# 200_CDH_USB_2_Hub.net
KiCad netlist of a schematic drawn in Altium Designer
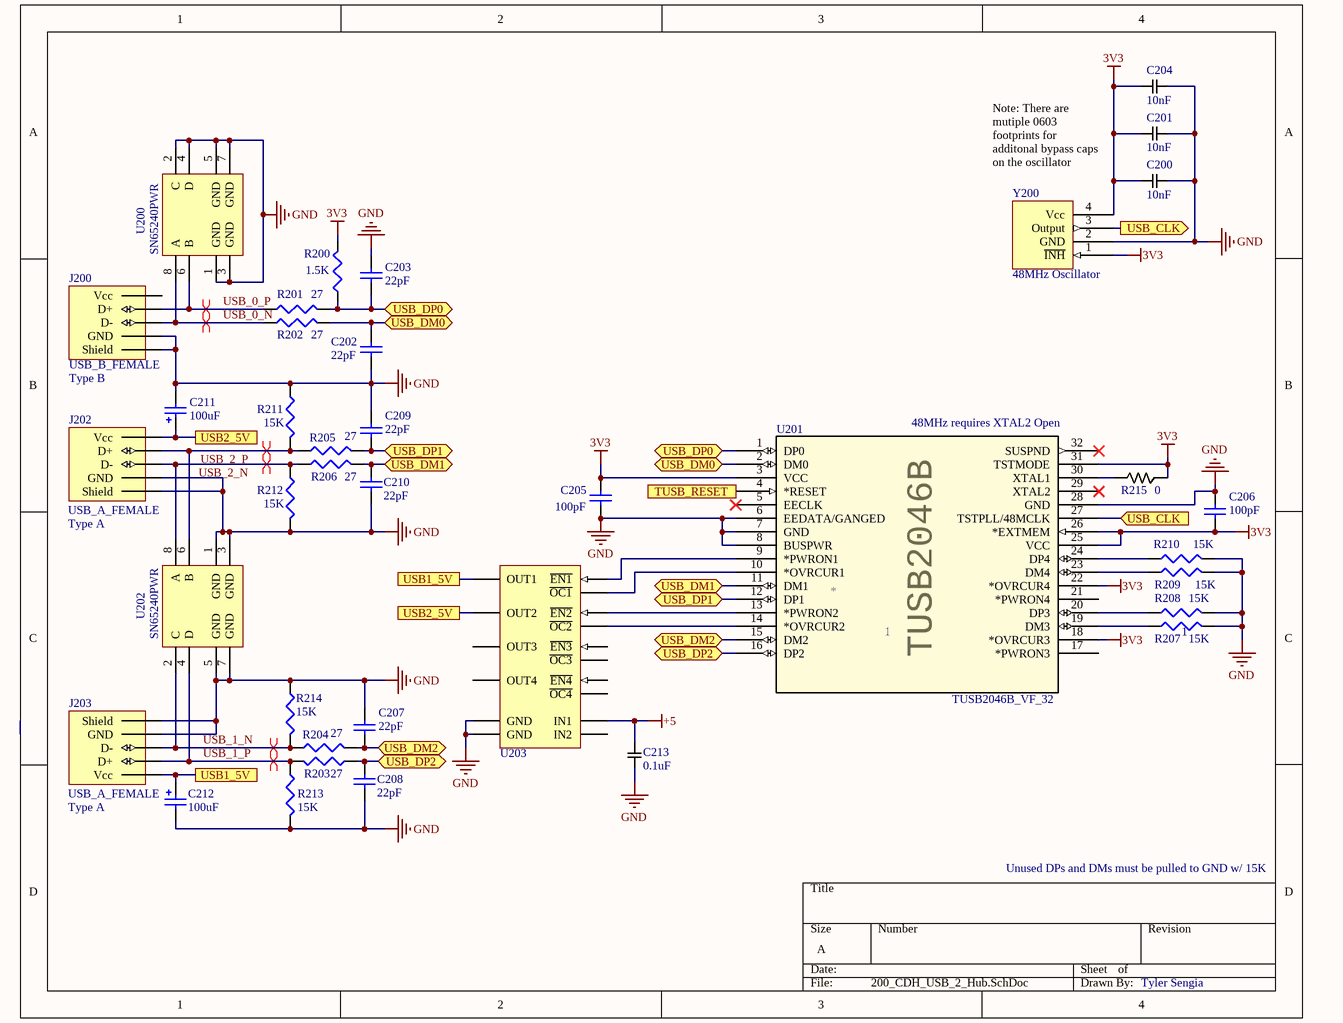
[diagram p0: 200_CDH_USB_2_Hub.SchDoc]

(export (version "E")
  (design (tool "Eeschema 10.0.6"))
  (components
    (comp (ref "C200")
      (value "10nF")
      (footprint "IMPERIAL0603_Capacitor")
      (description "10nF Capacitor for crystal oscillator")
      (fields (field (name "MANUFACTURER") "AVX") (field (name "MANUFACTURER PART NUMBER") "06033C103J4Z2A"))
      (libsource (lib "OASIS_COMPONENTS_SYMBOLS") (part "06033C103J4Z2A"))
    )
    (comp (ref "C201")
      (value "10nF")
      (footprint "IMPERIAL0603_Capacitor")
      (description "10nF Capacitor for crystal oscillator")
      (fields (field (name "MANUFACTURER") "AVX") (field (name "MANUFACTURER PART NUMBER") "06033C103J4Z2A"))
      (libsource (lib "OASIS_COMPONENTS_SYMBOLS") (part "06033C103J4Z2A"))
    )
    (comp (ref "C202")
      (value "22pF")
      (footprint "IMPERIAL0805_CAPACITOR")
      (description "22pF USB Filter Capacitor")
      (fields (field (name "Comment") "22pF capacitor") (field (name "PUBLISHER") "Altium Limited"))
      (libsource (lib "TUSB_SYMBOLS") (part "C0805X220K3GACAUTO"))
    )
    (comp (ref "C203")
      (value "22pF")
      (footprint "IMPERIAL0805_CAPACITOR")
      (description "22pF USB Filter Capacitor")
      (fields (field (name "Comment") "22pF capacitor") (field (name "PUBLISHER") "Altium Limited"))
      (libsource (lib "TUSB_SYMBOLS") (part "C0805X220K3GACAUTO"))
    )
    (comp (ref "C204")
      (value "10nF")
      (footprint "IMPERIAL0603_Capacitor")
      (description "10nF Capacitor for crystal oscillator")
      (fields (field (name "MANUFACTURER") "AVX") (field (name "MANUFACTURER PART NUMBER") "06033C103J4Z2A"))
      (libsource (lib "OASIS_COMPONENTS_SYMBOLS") (part "06033C103J4Z2A"))
    )
    (comp (ref "C205")
      (value "100pF")
      (footprint "IMPERIAL0603_Capacitor")
      (description "100pF Cap for IC Vcc Smoothing")
      (fields (field (name "Comment") "100pF Capacitor") (field (name "PUBLISHER") "Altium Limited"))
      (libsource (lib "TUSB_SYMBOLS") (part "C0603C101K8HAUTO"))
    )
    (comp (ref "C206")
      (value "100pF")
      (footprint "IMPERIAL0603_Capacitor")
      (description "100pF Cap for IC Vcc Smoothing")
      (fields (field (name "Comment") "100pF Capacitor") (field (name "PUBLISHER") "Altium Limited"))
      (libsource (lib "TUSB_SYMBOLS") (part "C0603C101K8HAUTO"))
    )
    (comp (ref "C207")
      (value "22pF")
      (footprint "IMPERIAL0805_CAPACITOR")
      (description "22pF USB Filter Capacitor")
      (fields (field (name "Comment") "22pF capacitor") (field (name "PUBLISHER") "Altium Limited"))
      (libsource (lib "TUSB_SYMBOLS") (part "C0805X220K3GACAUTO"))
    )
    (comp (ref "C208")
      (value "22pF")
      (footprint "IMPERIAL0805_CAPACITOR")
      (description "22pF USB Filter Capacitor")
      (fields (field (name "Comment") "22pF capacitor") (field (name "PUBLISHER") "Altium Limited"))
      (libsource (lib "TUSB_SYMBOLS") (part "C0805X220K3GACAUTO"))
    )
    (comp (ref "C209")
      (value "22pF")
      (footprint "IMPERIAL0805_CAPACITOR")
      (description "22pF USB Filter Capacitor")
      (fields (field (name "Comment") "22pF capacitor") (field (name "PUBLISHER") "Altium Limited"))
      (libsource (lib "TUSB_SYMBOLS") (part "C0805X220K3GACAUTO"))
    )
    (comp (ref "C210")
      (value "22pF")
      (footprint "IMPERIAL0805_CAPACITOR")
      (description "22pF USB Filter Capacitor")
      (fields (field (name "Comment") "22pF capacitor") (field (name "PUBLISHER") "Altium Limited"))
      (libsource (lib "TUSB_SYMBOLS") (part "C0805X220K3GACAUTO"))
    )
    (comp (ref "C211")
      (value "100uF")
      (footprint "POLAR_CAP_SMD_EIA2010")
      (description "100uF, USB Power smoothing capacitor, tantalium, low ESR")
      (fields (field (name "Comment") "F910J107MBAAJ6") (field (name "PUBLISHER") "Altium Limited"))
      (libsource (lib "TUSB_SYMBOLS") (part "F910J107MBAAJ6"))
    )
    (comp (ref "C212")
      (value "100uF")
      (footprint "POLAR_CAP_SMD_EIA2010")
      (description "100uF, USB Power smoothing capacitor, tantalium, low ESR")
      (fields (field (name "Comment") "F910J107MBAAJ6") (field (name "PUBLISHER") "Altium Limited"))
      (libsource (lib "TUSB_SYMBOLS") (part "F910J107MBAAJ6"))
    )
    (comp (ref "C213")
      (value "0.1uF")
      (footprint "IMPERIAL0603_Capacitor")
      (description "0.1uF Capacitor, Non Polarized Chip Cap")
      (fields (field (name "Comment") "0.1uF Capacitor"))
      (libsource (lib "OASIS_COMPONENTS_SYMBOLS") (part "VJ0603Y104MXQPW1BC"))
    )
    (comp (ref "J200")
      (value "USB_B_FEMALE")
      (footprint "USB_B_FEMALE_RT")
      (description "USB Type B female connector.")
      (fields (field (name "USB TYPE") "Type B"))
      (libsource (lib "OASIS_COMPONENTS_SYMBOLS") (part "USB_B_FEMALE"))
    )
    (comp (ref "J202")
      (value "USB_A_FEMALE")
      (footprint "USB_A_FEMALE_SINGLE")
      (description "USB Type A female connector.")
      (fields (field (name "USB TYPE") "Type A"))
      (libsource (lib "TUSB_SYMBOLS") (part "USB_A_FEMALE"))
    )
    (comp (ref "J203")
      (value "USB_A_FEMALE")
      (footprint "USB_A_FEMALE_SINGLE")
      (description "USB Type A female connector.")
      (fields (field (name "USB TYPE") "Type A"))
      (libsource (lib "") (part "USB_A_FEMALE_1"))
    )
    (comp (ref "R200")
      (value "1.5K")
      (footprint "Imperial0603_RES")
      (description "1.5KOhm Resistor, for USB pull up")
      (fields (field (name "Comment") "1.5KOhm Resistor") (field (name "PUBLISHER") "Altium Limited"))
      (libsource (lib "OASIS_COMPONENTS_SYMBOLS") (part "ERJ-S03D1501V"))
    )
    (comp (ref "R201")
      (value "27")
      (footprint "Imperial0805_RES")
      (description "27Ohm Resitor, USB Terminating Resistor")
      (fields (field (name "Comment") "27 Ohm Resistor") (field (name "PUBLISHER") "Altium Limited"))
      (libsource (lib "TUSB_SYMBOLS") (part "CR0805-FX-27R0ELF"))
    )
    (comp (ref "R202")
      (value "27")
      (footprint "Imperial0805_RES")
      (description "27Ohm Resitor, USB Terminating Resistor")
      (fields (field (name "Comment") "27 Ohm Resistor") (field (name "PUBLISHER") "Altium Limited"))
      (libsource (lib "TUSB_SYMBOLS") (part "CR0805-FX-27R0ELF"))
    )
    (comp (ref "R203")
      (value "27")
      (footprint "Imperial0805_RES")
      (description "27Ohm Resitor, USB Terminating Resistor")
      (fields (field (name "Comment") "27 Ohm Resistor") (field (name "PUBLISHER") "Altium Limited"))
      (libsource (lib "TUSB_SYMBOLS") (part "CR0805-FX-27R0ELF"))
    )
    (comp (ref "R204")
      (value "27")
      (footprint "Imperial0805_RES")
      (description "27Ohm Resitor, USB Terminating Resistor")
      (fields (field (name "Comment") "27 Ohm Resistor") (field (name "PUBLISHER") "Altium Limited"))
      (libsource (lib "TUSB_SYMBOLS") (part "CR0805-FX-27R0ELF"))
    )
    (comp (ref "R205")
      (value "27")
      (footprint "Imperial0805_RES")
      (description "27Ohm Resitor, USB Terminating Resistor")
      (fields (field (name "Comment") "27 Ohm Resistor") (field (name "PUBLISHER") "Altium Limited"))
      (libsource (lib "TUSB_SYMBOLS") (part "CR0805-FX-27R0ELF"))
    )
    (comp (ref "R206")
      (value "27")
      (footprint "Imperial0805_RES")
      (description "27Ohm Resitor, USB Terminating Resistor")
      (fields (field (name "Comment") "27 Ohm Resistor") (field (name "PUBLISHER") "Altium Limited"))
      (libsource (lib "TUSB_SYMBOLS") (part "CR0805-FX-27R0ELF"))
    )
    (comp (ref "R207")
      (value "15K")
      (footprint "Imperial0603_RES")
      (description "15KOhm Resistor, for USB pull down")
      (fields (field (name "Comment") "15KOhm Resistor") (field (name "PUBLISHER") "Altium Limited"))
      (libsource (lib "TUSB_SYMBOLS") (part "CRCW060315K0JNEAC"))
    )
    (comp (ref "R208")
      (value "15K")
      (footprint "Imperial0603_RES")
      (description "15KOhm Resistor, for USB pull down")
      (fields (field (name "Comment") "15KOhm Resistor") (field (name "PUBLISHER") "Altium Limited"))
      (libsource (lib "TUSB_SYMBOLS") (part "CRCW060315K0JNEAC"))
    )
    (comp (ref "R209")
      (value "15K")
      (footprint "Imperial0603_RES")
      (description "15KOhm Resistor, for USB pull down")
      (fields (field (name "Comment") "15KOhm Resistor") (field (name "PUBLISHER") "Altium Limited"))
      (libsource (lib "TUSB_SYMBOLS") (part "CRCW060315K0JNEAC"))
    )
    (comp (ref "R210")
      (value "15K")
      (footprint "Imperial0603_RES")
      (description "15KOhm Resistor, for USB pull down")
      (fields (field (name "Comment") "15KOhm Resistor") (field (name "PUBLISHER") "Altium Limited"))
      (libsource (lib "TUSB_SYMBOLS") (part "CRCW060315K0JNEAC"))
    )
    (comp (ref "R211")
      (value "15K")
      (footprint "Imperial0603_RES")
      (description "15KOhm Resistor, for USB pull down")
      (fields (field (name "Comment") "15KOhm Resistor") (field (name "PUBLISHER") "Altium Limited"))
      (libsource (lib "TUSB_SYMBOLS") (part "CRCW060315K0JNEAC"))
    )
    (comp (ref "R212")
      (value "15K")
      (footprint "Imperial0603_RES")
      (description "15KOhm Resistor, for USB pull down")
      (fields (field (name "Comment") "15KOhm Resistor") (field (name "PUBLISHER") "Altium Limited"))
      (libsource (lib "TUSB_SYMBOLS") (part "CRCW060315K0JNEAC"))
    )
    (comp (ref "R213")
      (value "15K")
      (footprint "Imperial0603_RES")
      (description "15KOhm Resistor, for USB pull down")
      (fields (field (name "Comment") "15KOhm Resistor") (field (name "PUBLISHER") "Altium Limited"))
      (libsource (lib "TUSB_SYMBOLS") (part "CRCW060315K0JNEAC"))
    )
    (comp (ref "R214")
      (value "15K")
      (footprint "Imperial0603_RES")
      (description "15KOhm Resistor, for USB pull down")
      (fields (field (name "Comment") "15KOhm Resistor") (field (name "PUBLISHER") "Altium Limited"))
      (libsource (lib "TUSB_SYMBOLS") (part "CRCW060315K0JNEAC"))
    )
    (comp (ref "R215")
      (value "0")
      (footprint "Imperial0603_RES")
      (description "Placeholder 0 Ohm Link.")
      (fields (field (name "Comment") "0 Ohm Link"))
      (libsource (lib "OASIS_COMPONENTS_SYMBOLS") (part "0_Ohm_Link"))
    )
    (comp (ref "U200")
      (value "SN65240PWR")
      (footprint "PW0008A_M")
      (fields (field (name "MANUFACTURER") "Texas Instruments"))
      (libsource (lib "OASIS_COMPONENTS_SYMBOLS") (part "CMP-0326-00072-3"))
    )
    (comp (ref "U201")
      (value "TUSB2046B_VF_32")
      (footprint "TQFP80P900X900X160-32N")
      (description "USB 2.0 Hub IC")
      (fields
        (field (name "MANUFACTURER_PART_NUMBER") "tusb2046b_vf_32")
        (field (name "MANUFACTURER") "Texas Instruments")
        (field (name "GENERIC_PART_NUMBER") "TUSB2046B")
      )
      (libsource (lib "OASIS_COMPONENTS_SYMBOLS") (part "TUSB2046B_VF_32"))
    )
    (comp (ref "U202")
      (value "SN65240PWR")
      (footprint "PW0008A_M")
      (fields (field (name "MANUFACTURER") "Texas Instruments"))
      (libsource (lib "") (part "CMP-0326-00072-3_1"))
    )
    (comp (ref "U203")
      (value "TPS2044BDR")
      (footprint "D0016A_M_Local")
      (fields (field (name "MANUFACTURER") "Texas Instruments"))
      (libsource (lib "OASIS_COMPONENTS_SYMBOLS") (part "TITPS10244BD1"))
    )
    (comp (ref "Y200")
      (value "48MHz Oscillator")
      (footprint "KC3225-C3")
      (description "48MHz crystal oscillator")
      (libsource (lib "OASIS_COMPONENTS_SYMBOLS") (part "KC3225A-C3"))
    )
  )
  (nets
    (net (code "1") (name "+5") (class "Default")
      (node (ref "C213") (pin "2") (pinfunction "2_2") (pintype "passive"))
      (node (ref "U203") (pin "2") (pinfunction "IN1_2") (pintype "power_in"))
    )
    (net (code "2") (name "/TUSB_RESET") (class "Default")
      (node (ref "U201") (pin "4") (pinfunction "*RESET_4") (pintype "input"))
    )
    (net (code "3") (name "/USB1_5V") (class "Default")
      (node (ref "C212") (pin "1") (pinfunction "1_1") (pintype "passive"))
      (node (ref "J203") (pin "Vcc") (pinfunction "Vcc_Vcc") (pintype "power_in"))
      (node (ref "U203") (pin "15") (pinfunction "OUT1_15") (pintype "power_in"))
    )
    (net (code "4") (name "/USB2_5V") (class "Default")
      (node (ref "C211") (pin "1") (pinfunction "1_1") (pintype "passive"))
      (node (ref "J202") (pin "Vcc") (pinfunction "Vcc_Vcc") (pintype "power_in"))
      (node (ref "U203") (pin "14") (pinfunction "OUT2_14") (pintype "power_in"))
    )
    (net (code "5") (name "/USB_0_N") (class "Default")
      (node (ref "J200") (pin "D-") (pinfunction "D-_D-") (pintype "bidirectional"))
      (node (ref "R202") (pin "1") (pinfunction "1_1") (pintype "passive"))
      (node (ref "U200") (pin "8") (pinfunction "A_8") (pintype "passive"))
    )
    (net (code "6") (name "/USB_0_P") (class "Default")
      (node (ref "J200") (pin "D+") (pinfunction "D+_D+") (pintype "bidirectional"))
      (node (ref "R201") (pin "1") (pinfunction "1_1") (pintype "passive"))
      (node (ref "U200") (pin "6") (pinfunction "B_6") (pintype "passive"))
    )
    (net (code "7") (name "/USB_1_N") (class "Default")
      (node (ref "J203") (pin "D-") (pinfunction "D-_D-") (pintype "bidirectional"))
      (node (ref "R204") (pin "2") (pinfunction "2_2") (pintype "passive"))
      (node (ref "R214") (pin "1") (pinfunction "1_1") (pintype "passive"))
      (node (ref "U202") (pin "2") (pinfunction "C_2") (pintype "passive"))
    )
    (net (code "8") (name "/USB_1_P") (class "Default")
      (node (ref "J203") (pin "D+") (pinfunction "D+_D+") (pintype "bidirectional"))
      (node (ref "R203") (pin "1") (pinfunction "1_1") (pintype "passive"))
      (node (ref "R213") (pin "2") (pinfunction "2_2") (pintype "passive"))
      (node (ref "U202") (pin "4") (pinfunction "D_4") (pintype "passive"))
    )
    (net (code "9") (name "/USB_2_N") (class "Default")
      (node (ref "J202") (pin "D-") (pinfunction "D-_D-") (pintype "bidirectional"))
      (node (ref "R206") (pin "1") (pinfunction "1_1") (pintype "passive"))
      (node (ref "R212") (pin "1") (pinfunction "1_1") (pintype "passive"))
      (node (ref "U202") (pin "8") (pinfunction "A_8") (pintype "passive"))
    )
    (net (code "10") (name "/USB_2_P") (class "Default")
      (node (ref "J202") (pin "D+") (pinfunction "D+_D+") (pintype "bidirectional"))
      (node (ref "R205") (pin "1") (pinfunction "1_1") (pintype "passive"))
      (node (ref "R211") (pin "2") (pinfunction "2_2") (pintype "passive"))
      (node (ref "U202") (pin "6") (pinfunction "B_6") (pintype "passive"))
    )
    (net (code "11") (name "/USB_CLK") (class "Default")
      (node (ref "U201") (pin "27") (pinfunction "TSTPLL/48MCLK_27") (pintype "passive"))
      (node (ref "Y200") (pin "3") (pinfunction "Output_3") (pintype "output"))
    )
    (net (code "12") (name "/USB_DM0") (class "Default")
      (node (ref "C202") (pin "2") (pinfunction "2_2") (pintype "passive"))
      (node (ref "R202") (pin "2") (pinfunction "2_2") (pintype "passive"))
      (node (ref "U201") (pin "2") (pinfunction "DM0_2") (pintype "bidirectional"))
    )
    (net (code "13") (name "/USB_DM1") (class "Default")
      (node (ref "C210") (pin "1") (pinfunction "1_1") (pintype "passive"))
      (node (ref "R206") (pin "2") (pinfunction "2_2") (pintype "passive"))
      (node (ref "U201") (pin "11") (pinfunction "DM1_11") (pintype "bidirectional"))
    )
    (net (code "14") (name "/USB_DM2") (class "Default")
      (node (ref "C207") (pin "2") (pinfunction "2_2") (pintype "passive"))
      (node (ref "R204") (pin "1") (pinfunction "1_1") (pintype "passive"))
      (node (ref "U201") (pin "15") (pinfunction "DM2_15") (pintype "bidirectional"))
    )
    (net (code "15") (name "/USB_DP0") (class "Default")
      (node (ref "C203") (pin "1") (pinfunction "1_1") (pintype "passive"))
      (node (ref "R200") (pin "1") (pinfunction "1_1") (pintype "passive"))
      (node (ref "R201") (pin "2") (pinfunction "2_2") (pintype "passive"))
      (node (ref "U201") (pin "1") (pinfunction "DP0_1") (pintype "bidirectional"))
    )
    (net (code "16") (name "/USB_DP1") (class "Default")
      (node (ref "C209") (pin "2") (pinfunction "2_2") (pintype "passive"))
      (node (ref "R205") (pin "2") (pinfunction "2_2") (pintype "passive"))
      (node (ref "U201") (pin "12") (pinfunction "DP1_12") (pintype "bidirectional"))
    )
    (net (code "17") (name "/USB_DP2") (class "Default")
      (node (ref "C208") (pin "1") (pinfunction "1_1") (pintype "passive"))
      (node (ref "R203") (pin "2") (pinfunction "2_2") (pintype "passive"))
      (node (ref "U201") (pin "16") (pinfunction "DP2_16") (pintype "bidirectional"))
    )
    (net (code "18") (name "3V3") (class "Default")
      (node (ref "C200") (pin "2") (pinfunction "2_2") (pintype "passive"))
      (node (ref "C201") (pin "2") (pinfunction "2_2") (pintype "passive"))
      (node (ref "C204") (pin "2") (pinfunction "2_2") (pintype "passive"))
      (node (ref "C205") (pin "2") (pinfunction "2_2") (pintype "passive"))
      (node (ref "C206") (pin "1") (pinfunction "1_1") (pintype "passive"))
      (node (ref "R200") (pin "2") (pinfunction "2_2") (pintype "passive"))
      (node (ref "R215") (pin "2") (pinfunction "2_2") (pintype "passive"))
      (node (ref "U201") (pin "18") (pinfunction "*OVRCUR3_18") (pintype "passive"))
      (node (ref "U201") (pin "22") (pinfunction "*OVRCUR4_22") (pintype "passive"))
      (node (ref "U201") (pin "25") (pinfunction "VCC_25") (pintype "power_in"))
      (node (ref "U201") (pin "26") (pinfunction "*EXTMEM_26") (pintype "input"))
      (node (ref "U201") (pin "3") (pinfunction "VCC_3") (pintype "power_in"))
      (node (ref "U201") (pin "31") (pinfunction "TSTMODE_31") (pintype "passive"))
      (node (ref "Y200") (pin "1") (pinfunction "~{INH}_1") (pintype "input"))
      (node (ref "Y200") (pin "4") (pinfunction "Vcc_4") (pintype "power_in"))
    )
    (net (code "19") (name "GND") (class "Default")
      (node (ref "C200") (pin "1") (pinfunction "1_1") (pintype "passive"))
      (node (ref "C201") (pin "1") (pinfunction "1_1") (pintype "passive"))
      (node (ref "C202") (pin "1") (pinfunction "1_1") (pintype "passive"))
      (node (ref "C203") (pin "2") (pinfunction "2_2") (pintype "passive"))
      (node (ref "C204") (pin "1") (pinfunction "1_1") (pintype "passive"))
      (node (ref "C205") (pin "1") (pinfunction "1_1") (pintype "passive"))
      (node (ref "C206") (pin "2") (pinfunction "2_2") (pintype "passive"))
      (node (ref "C207") (pin "1") (pinfunction "1_1") (pintype "passive"))
      (node (ref "C208") (pin "2") (pinfunction "2_2") (pintype "passive"))
      (node (ref "C209") (pin "1") (pinfunction "1_1") (pintype "passive"))
      (node (ref "C210") (pin "2") (pinfunction "2_2") (pintype "passive"))
      (node (ref "C211") (pin "2") (pinfunction "2_2") (pintype "passive"))
      (node (ref "C212") (pin "2") (pinfunction "2_2") (pintype "passive"))
      (node (ref "C213") (pin "1") (pinfunction "1_1") (pintype "passive"))
      (node (ref "J200") (pin "GND") (pinfunction "GND_GND") (pintype "passive"))
      (node (ref "J200") (pin "Shield") (pinfunction "Shield_Shield") (pintype "passive"))
      (node (ref "J202") (pin "GND") (pinfunction "GND_GND") (pintype "passive"))
      (node (ref "J202") (pin "Shield") (pinfunction "Shield_Shield") (pintype "passive"))
      (node (ref "J203") (pin "GND") (pinfunction "GND_GND") (pintype "passive"))
      (node (ref "J203") (pin "Shield") (pinfunction "Shield_Shield") (pintype "passive"))
      (node (ref "R207") (pin "2") (pinfunction "2_2") (pintype "passive"))
      (node (ref "R208") (pin "2") (pinfunction "2_2") (pintype "passive"))
      (node (ref "R209") (pin "2") (pinfunction "2_2") (pintype "passive"))
      (node (ref "R210") (pin "2") (pinfunction "2_2") (pintype "passive"))
      (node (ref "R211") (pin "1") (pinfunction "1_1") (pintype "passive"))
      (node (ref "R212") (pin "2") (pinfunction "2_2") (pintype "passive"))
      (node (ref "R213") (pin "1") (pinfunction "1_1") (pintype "passive"))
      (node (ref "R214") (pin "2") (pinfunction "2_2") (pintype "passive"))
      (node (ref "U200") (pin "1") (pinfunction "GND_1") (pintype "power_in"))
      (node (ref "U200") (pin "2") (pinfunction "C_2") (pintype "passive"))
      (node (ref "U200") (pin "3") (pinfunction "GND_3") (pintype "power_in"))
      (node (ref "U200") (pin "4") (pinfunction "D_4") (pintype "passive"))
      (node (ref "U200") (pin "5") (pinfunction "GND_5") (pintype "power_in"))
      (node (ref "U200") (pin "7") (pinfunction "GND_7") (pintype "power_in"))
      (node (ref "U201") (pin "28") (pinfunction "GND_28") (pintype "power_in"))
      (node (ref "U201") (pin "6") (pinfunction "EEDATA/GANGED_6") (pintype "passive"))
      (node (ref "U201") (pin "7") (pinfunction "GND_7") (pintype "power_in"))
      (node (ref "U201") (pin "8") (pinfunction "BUSPWR_8") (pintype "passive"))
      (node (ref "U202") (pin "1") (pinfunction "GND_1") (pintype "power_in"))
      (node (ref "U202") (pin "3") (pinfunction "GND_3") (pintype "power_in"))
      (node (ref "U202") (pin "5") (pinfunction "GND_5") (pintype "power_in"))
      (node (ref "U202") (pin "7") (pinfunction "GND_7") (pintype "power_in"))
      (node (ref "U203") (pin "1") (pinfunction "GND_1") (pintype "power_in"))
      (node (ref "U203") (pin "5") (pinfunction "GND_5") (pintype "power_in"))
      (node (ref "Y200") (pin "2") (pinfunction "GND_2") (pintype "power_in"))
    )
    (net (code "20") (name "Net-(U201-*OVRCUR1)") (class "Default")
      (node (ref "U201") (pin "10") (pinfunction "*OVRCUR1_10") (pintype "passive"))
      (node (ref "U203") (pin "16") (pinfunction "~{OC1}_16") (pintype "open_collector"))
    )
    (net (code "21") (name "Net-(U201-*OVRCUR2)") (class "Default")
      (node (ref "U201") (pin "14") (pinfunction "*OVRCUR2_14") (pintype "passive"))
      (node (ref "U203") (pin "13") (pinfunction "~{OC2}_13") (pintype "open_collector"))
    )
    (net (code "22") (name "Net-(U201-*PWRON1)") (class "Default")
      (node (ref "U201") (pin "9") (pinfunction "*PWRON1_9") (pintype "passive"))
      (node (ref "U203") (pin "3") (pinfunction "~{EN1}_3") (pintype "input"))
    )
    (net (code "23") (name "Net-(U201-*PWRON2)") (class "Default")
      (node (ref "U201") (pin "13") (pinfunction "*PWRON2_13") (pintype "passive"))
      (node (ref "U203") (pin "4") (pinfunction "~{EN2}_4") (pintype "input"))
    )
    (net (code "24") (name "Net-(U201-DM3)") (class "Default")
      (node (ref "R207") (pin "1") (pinfunction "1_1") (pintype "passive"))
      (node (ref "U201") (pin "19") (pinfunction "DM3_19") (pintype "bidirectional"))
    )
    (net (code "25") (name "Net-(U201-DM4)") (class "Default")
      (node (ref "R209") (pin "1") (pinfunction "1_1") (pintype "passive"))
      (node (ref "U201") (pin "23") (pinfunction "DM4_23") (pintype "bidirectional"))
    )
    (net (code "26") (name "Net-(U201-DP3)") (class "Default")
      (node (ref "R208") (pin "1") (pinfunction "1_1") (pintype "passive"))
      (node (ref "U201") (pin "20") (pinfunction "DP3_20") (pintype "bidirectional"))
    )
    (net (code "27") (name "Net-(U201-DP4)") (class "Default")
      (node (ref "R210") (pin "1") (pinfunction "1_1") (pintype "passive"))
      (node (ref "U201") (pin "24") (pinfunction "DP4_24") (pintype "bidirectional"))
    )
    (net (code "28") (name "Net-(U201-XTAL1)") (class "Default")
      (node (ref "R215") (pin "1") (pinfunction "1_1") (pintype "passive"))
      (node (ref "U201") (pin "30") (pinfunction "XTAL1_30") (pintype "passive"))
    )
    (net (code "29") (name "unconnected-(J200-PadVcc)") (class "Default")
      (node (ref "J200") (pin "Vcc") (pinfunction "Vcc_Vcc") (pintype "power_in"))
    )
    (net (code "30") (name "unconnected-(U201-*PWRON3-Pad17)") (class "Default")
      (node (ref "U201") (pin "17") (pinfunction "*PWRON3_17") (pintype "passive"))
    )
    (net (code "31") (name "unconnected-(U201-*PWRON4-Pad21)") (class "Default")
      (node (ref "U201") (pin "21") (pinfunction "*PWRON4_21") (pintype "passive"))
    )
    (net (code "32") (name "unconnected-(U201-EECLK-Pad5)") (class "Default")
      (node (ref "U201") (pin "5") (pinfunction "EECLK_5") (pintype "passive+no_connect"))
    )
    (net (code "33") (name "unconnected-(U201-SUSPND-Pad32)") (class "Default")
      (node (ref "U201") (pin "32") (pinfunction "SUSPND_32") (pintype "output+no_connect"))
    )
    (net (code "34") (name "unconnected-(U201-XTAL2-Pad29)") (class "Default")
      (node (ref "U201") (pin "29") (pinfunction "XTAL2_29") (pintype "passive+no_connect"))
    )
    (net (code "35") (name "unconnected-(U203-IN2-Pad6)") (class "Default")
      (node (ref "U203") (pin "6") (pinfunction "IN2_6") (pintype "power_in"))
    )
    (net (code "36") (name "unconnected-(U203-OUT3-Pad11)") (class "Default")
      (node (ref "U203") (pin "11") (pinfunction "OUT3_11") (pintype "power_in"))
    )
    (net (code "37") (name "unconnected-(U203-OUT4-Pad10)") (class "Default")
      (node (ref "U203") (pin "10") (pinfunction "OUT4_10") (pintype "power_in"))
    )
    (net (code "38") (name "unconnected-(U203-~{EN3}-Pad7)") (class "Default")
      (node (ref "U203") (pin "7") (pinfunction "~{EN3}_7") (pintype "input"))
    )
    (net (code "39") (name "unconnected-(U203-~{EN4}-Pad8)") (class "Default")
      (node (ref "U203") (pin "8") (pinfunction "~{EN4}_8") (pintype "input"))
    )
    (net (code "40") (name "unconnected-(U203-~{OC3}-Pad12)") (class "Default")
      (node (ref "U203") (pin "12") (pinfunction "~{OC3}_12") (pintype "open_collector"))
    )
    (net (code "41") (name "unconnected-(U203-~{OC4}-Pad9)") (class "Default")
      (node (ref "U203") (pin "9") (pinfunction "~{OC4}_9") (pintype "open_collector"))
    )
  )
)
